# transfer-interconnect.net
KiCad netlist of a schematic drawn in EAGLE
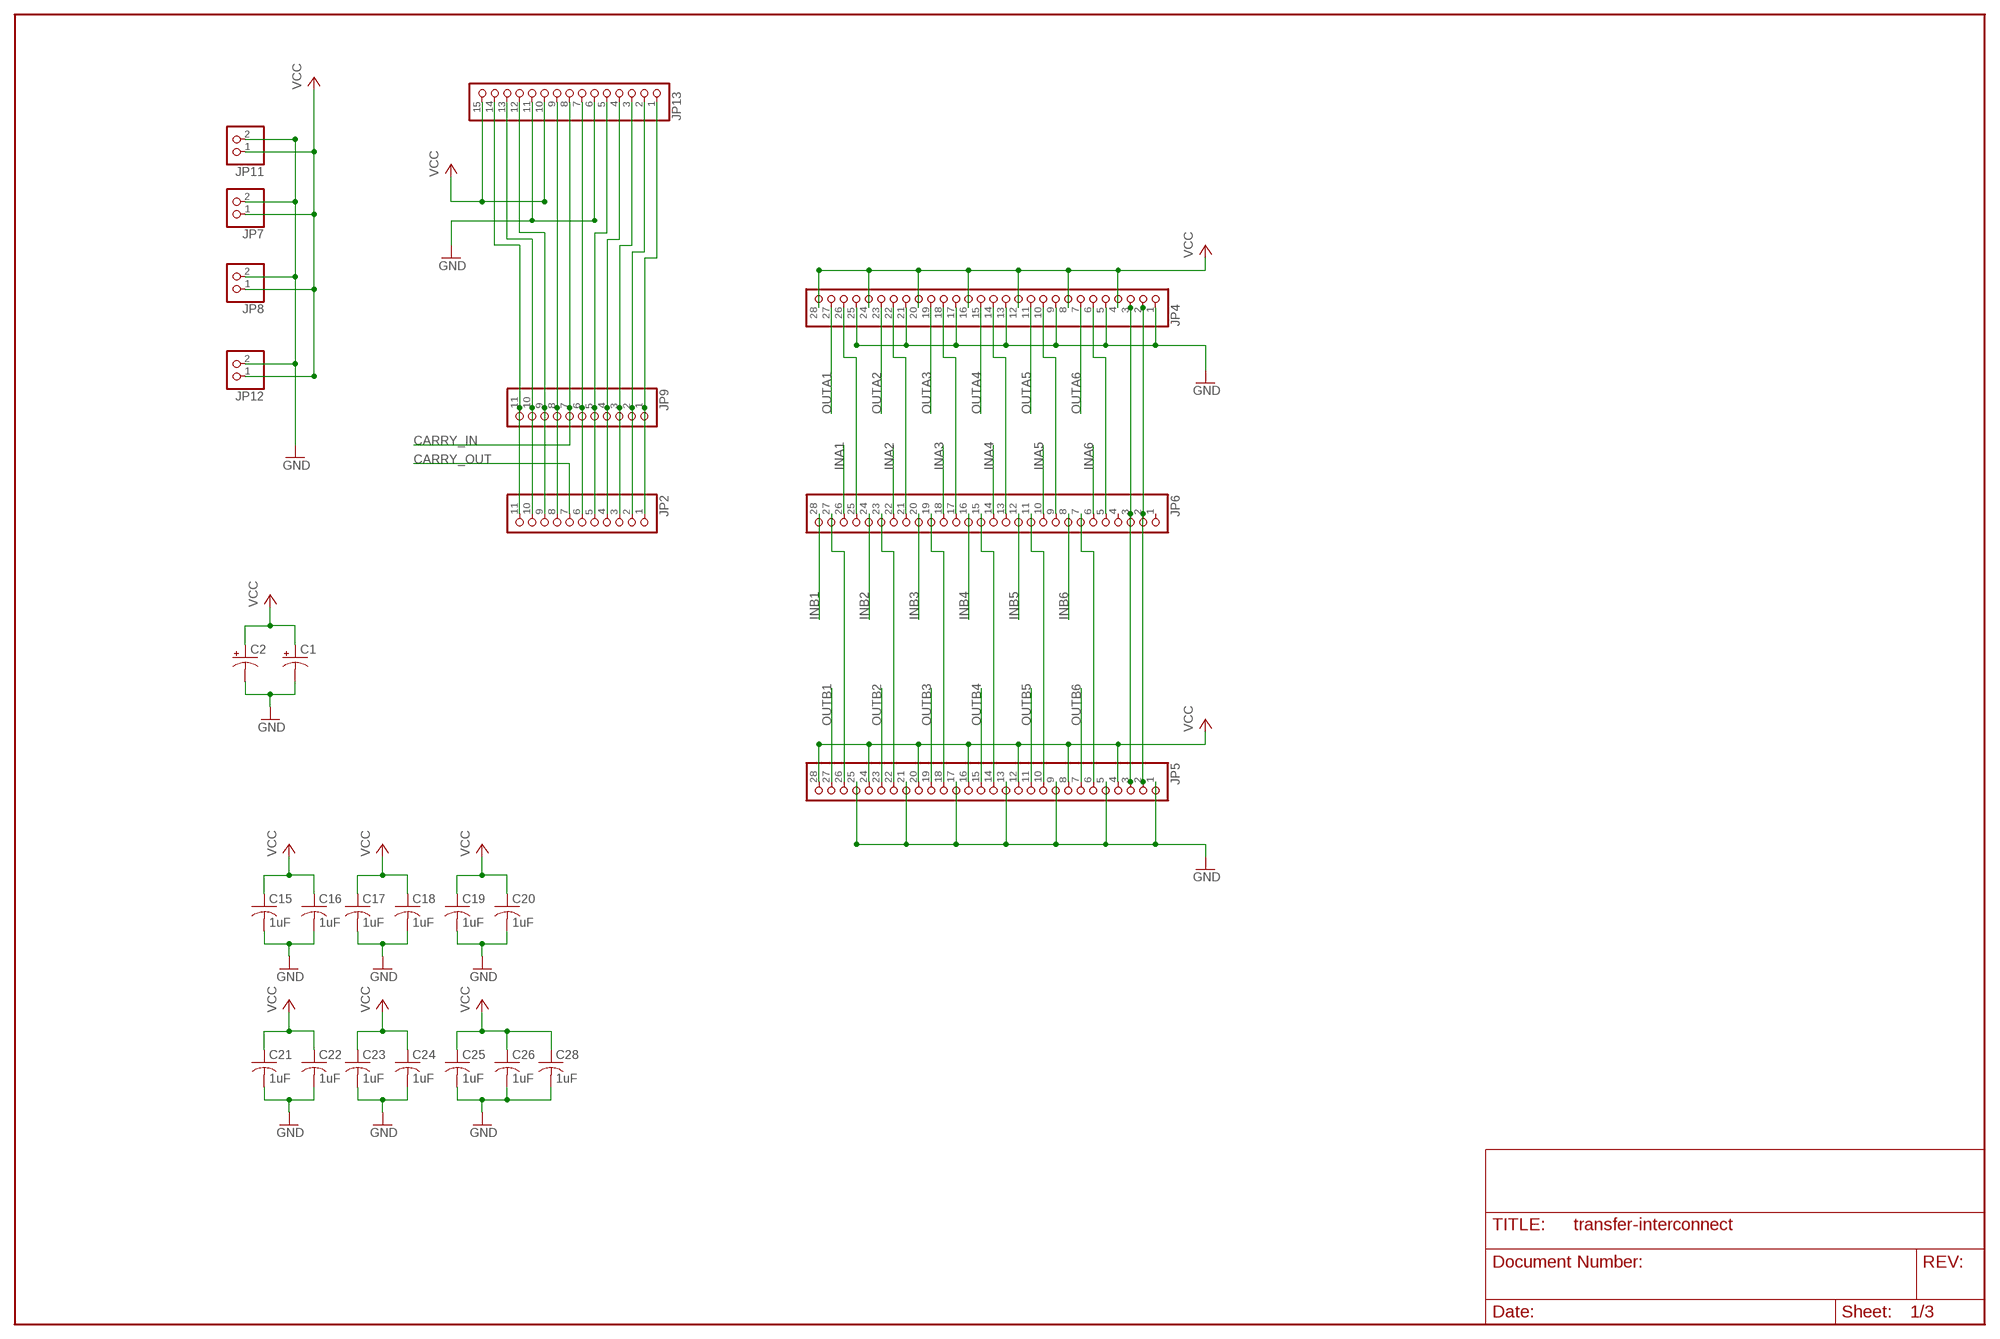
[diagram p0: schematic, sheet 1]
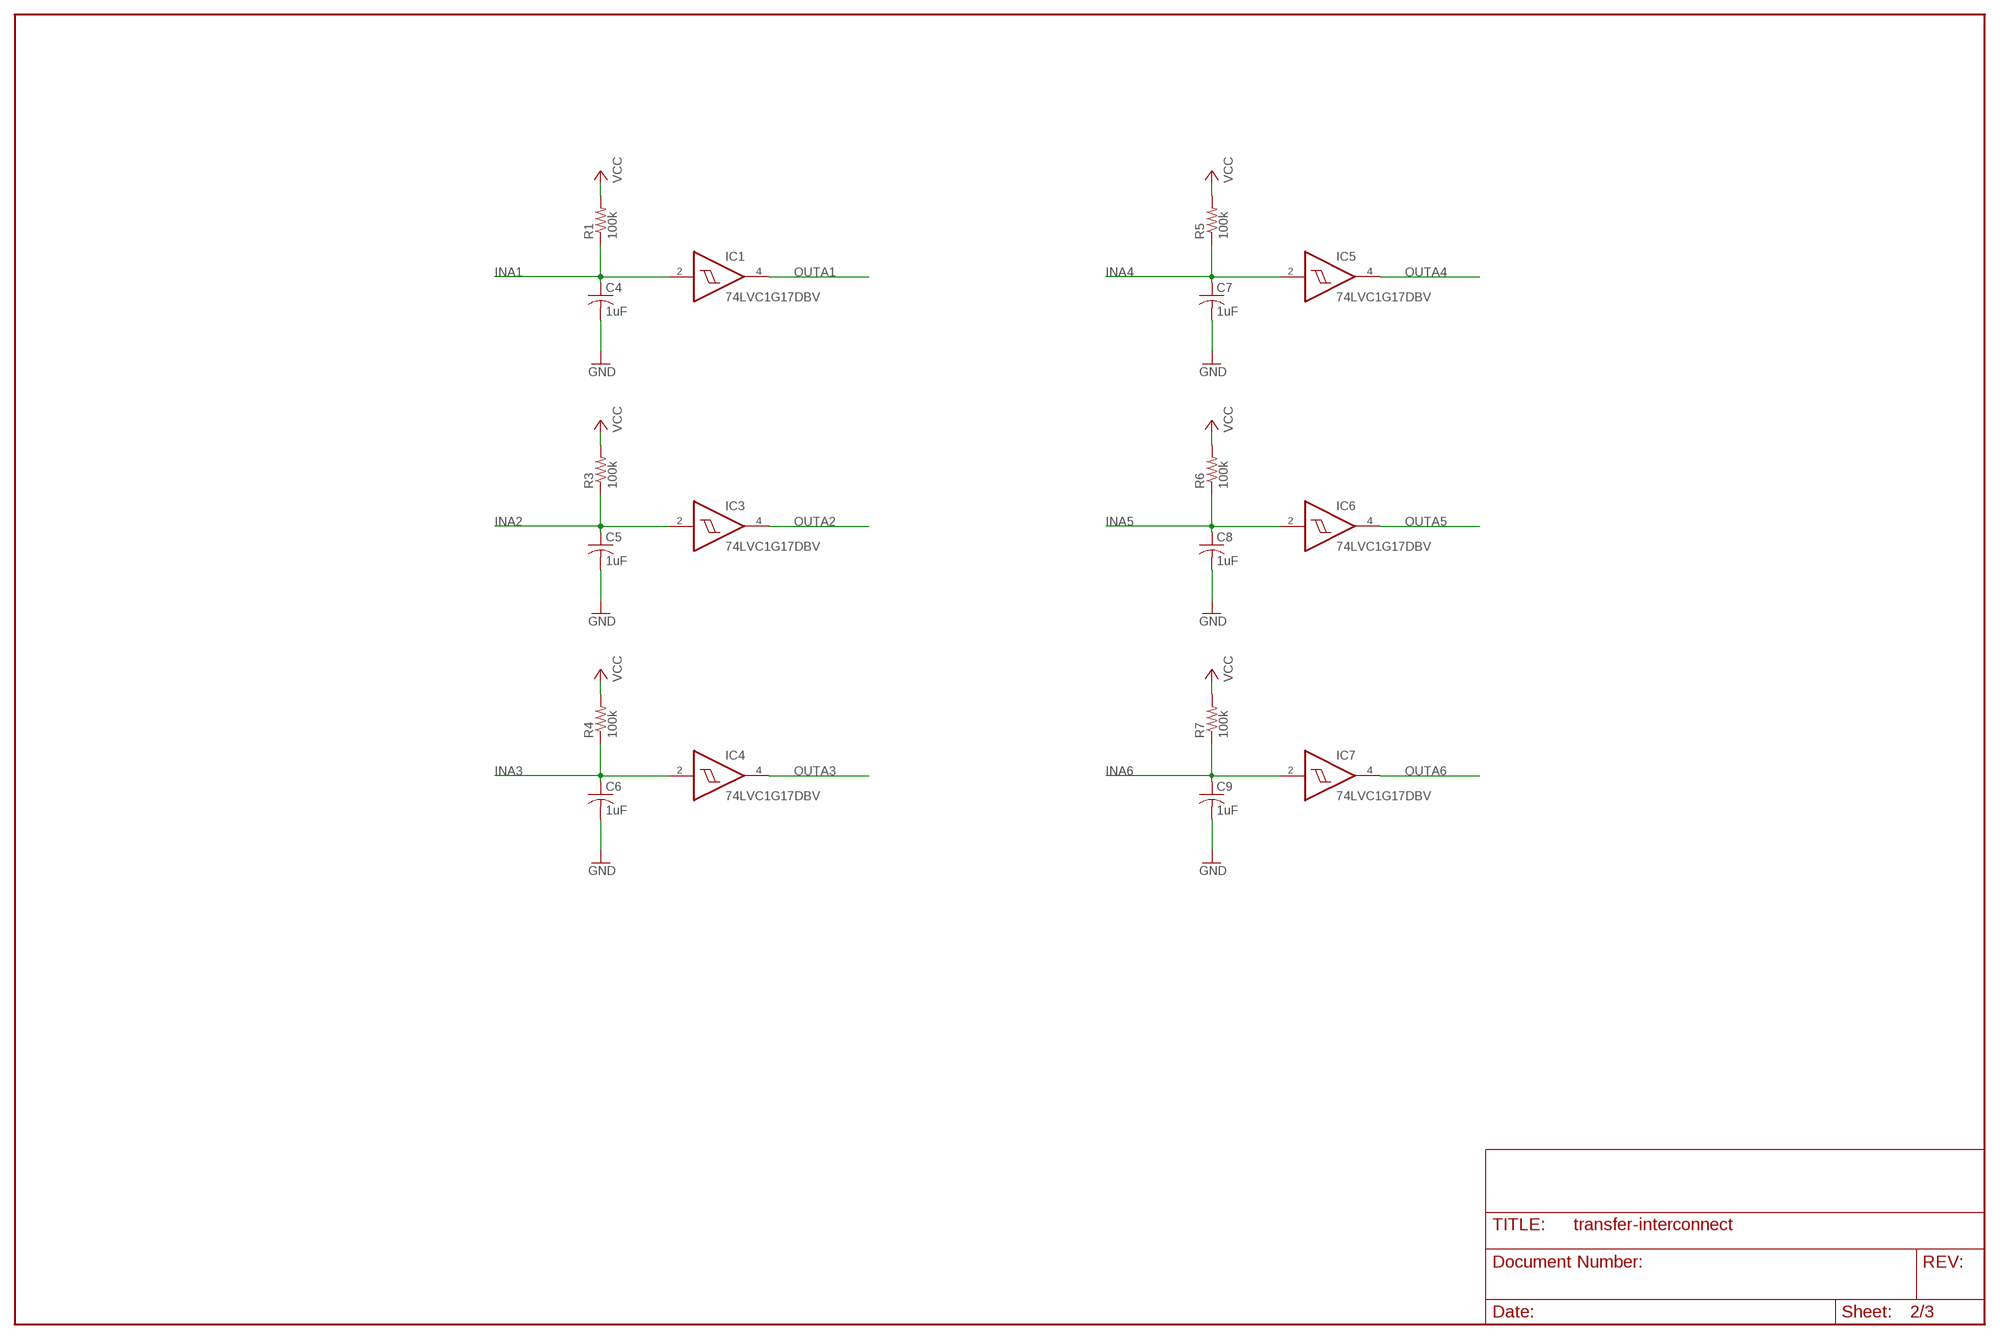
[diagram p1: schematic, sheet 2]
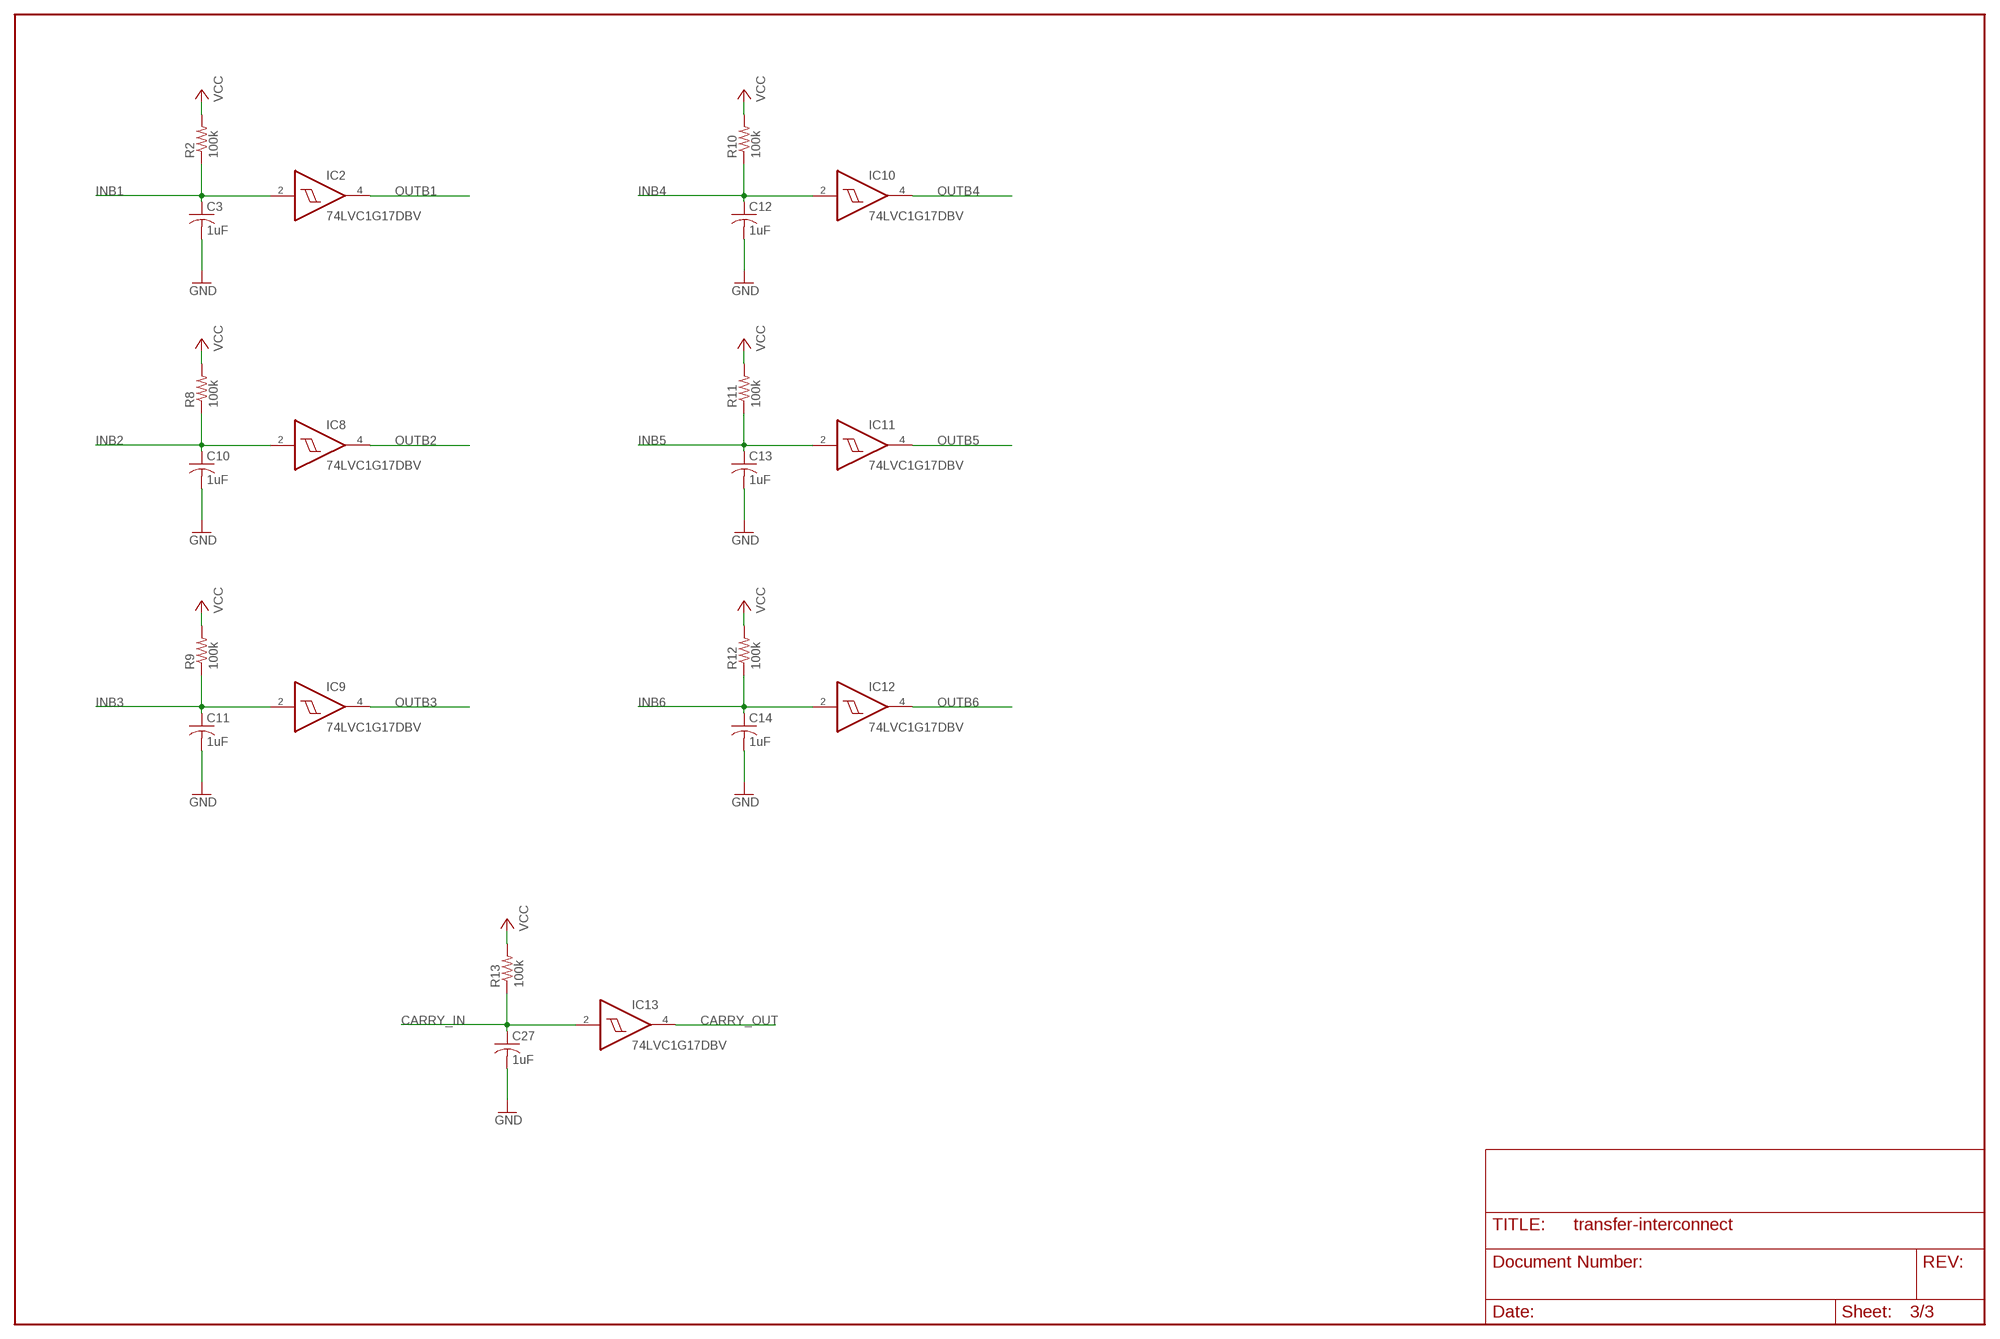
[diagram p2: schematic, sheet 3]

(export (version "E")
  (design (tool "Eeschema 10.0.6"))
  (components
    (comp (ref "C3")
      (value "1uF")
      (footprint "eagle-import:C0603K")
      (libsource (lib "eagle-import") (part "C-USC0603K"))
    )
    (comp (ref "C10")
      (value "1uF")
      (footprint "eagle-import:C0603K")
      (libsource (lib "eagle-import") (part "C-USC0603K"))
    )
    (comp (ref "C11")
      (value "1uF")
      (footprint "eagle-import:C0603K")
      (libsource (lib "eagle-import") (part "C-USC0603K"))
    )
    (comp (ref "C12")
      (value "1uF")
      (footprint "eagle-import:C0603K")
      (libsource (lib "eagle-import") (part "C-USC0603K"))
    )
    (comp (ref "C13")
      (value "1uF")
      (footprint "eagle-import:C0603K")
      (libsource (lib "eagle-import") (part "C-USC0603K"))
    )
    (comp (ref "C14")
      (value "1uF")
      (footprint "eagle-import:C0603K")
      (libsource (lib "eagle-import") (part "C-USC0603K"))
    )
    (comp (ref "C27")
      (value "1uF")
      (footprint "eagle-import:C0603K")
      (libsource (lib "eagle-import") (part "C-USC0603K"))
    )
    (comp (ref "IC2")
      (value "74LVC1G17DBV")
      (footprint "eagle-import:SOT23-5")
      (libsource (lib "eagle-import") (part "741G17DBVLVC"))
    )
    (comp (ref "IC8")
      (value "74LVC1G17DBV")
      (footprint "eagle-import:SOT23-5")
      (libsource (lib "eagle-import") (part "741G17DBVLVC"))
    )
    (comp (ref "IC9")
      (value "74LVC1G17DBV")
      (footprint "eagle-import:SOT23-5")
      (libsource (lib "eagle-import") (part "741G17DBVLVC"))
    )
    (comp (ref "IC10")
      (value "74LVC1G17DBV")
      (footprint "eagle-import:SOT23-5")
      (libsource (lib "eagle-import") (part "741G17DBVLVC"))
    )
    (comp (ref "IC11")
      (value "74LVC1G17DBV")
      (footprint "eagle-import:SOT23-5")
      (libsource (lib "eagle-import") (part "741G17DBVLVC"))
    )
    (comp (ref "IC12")
      (value "74LVC1G17DBV")
      (footprint "eagle-import:SOT23-5")
      (libsource (lib "eagle-import") (part "741G17DBVLVC"))
    )
    (comp (ref "IC13")
      (value "74LVC1G17DBV")
      (footprint "eagle-import:SOT23-5")
      (libsource (lib "eagle-import") (part "741G17DBVLVC"))
    )
    (comp (ref "R2")
      (value "100k")
      (footprint "eagle-import:R0603")
      (libsource (lib "eagle-import") (part "R-US_R0603"))
    )
    (comp (ref "R8")
      (value "100k")
      (footprint "eagle-import:R0603")
      (libsource (lib "eagle-import") (part "R-US_R0603"))
    )
    (comp (ref "R9")
      (value "100k")
      (footprint "eagle-import:R0603")
      (libsource (lib "eagle-import") (part "R-US_R0603"))
    )
    (comp (ref "R10")
      (value "100k")
      (footprint "eagle-import:R0603")
      (libsource (lib "eagle-import") (part "R-US_R0603"))
    )
    (comp (ref "R11")
      (value "100k")
      (footprint "eagle-import:R0603")
      (libsource (lib "eagle-import") (part "R-US_R0603"))
    )
    (comp (ref "R12")
      (value "100k")
      (footprint "eagle-import:R0603")
      (libsource (lib "eagle-import") (part "R-US_R0603"))
    )
    (comp (ref "R13")
      (value "100k")
      (footprint "eagle-import:R0603")
      (libsource (lib "eagle-import") (part "R-US_R0603"))
    )
    (comp (ref "C1")
      (value "CPOL-USE15-6AXIAL")
      (footprint "eagle-import:E15-6")
      (libsource (lib "eagle-import") (part "CPOL-USE15-6AXIAL"))
    )
    (comp (ref "C2")
      (value "CPOL-USE15-6AXIAL")
      (footprint "eagle-import:E15-6")
      (libsource (lib "eagle-import") (part "CPOL-USE15-6AXIAL"))
    )
    (comp (ref "C15")
      (value "1uF")
      (footprint "eagle-import:C0603K")
      (libsource (lib "eagle-import") (part "C-USC0603K"))
    )
    (comp (ref "C16")
      (value "1uF")
      (footprint "eagle-import:C0603K")
      (libsource (lib "eagle-import") (part "C-USC0603K"))
    )
    (comp (ref "C17")
      (value "1uF")
      (footprint "eagle-import:C0603K")
      (libsource (lib "eagle-import") (part "C-USC0603K"))
    )
    (comp (ref "C18")
      (value "1uF")
      (footprint "eagle-import:C0603K")
      (libsource (lib "eagle-import") (part "C-USC0603K"))
    )
    (comp (ref "C19")
      (value "1uF")
      (footprint "eagle-import:C0603K")
      (libsource (lib "eagle-import") (part "C-USC0603K"))
    )
    (comp (ref "C20")
      (value "1uF")
      (footprint "eagle-import:C0603K")
      (libsource (lib "eagle-import") (part "C-USC0603K"))
    )
    (comp (ref "C21")
      (value "1uF")
      (footprint "eagle-import:C0603K")
      (libsource (lib "eagle-import") (part "C-USC0603K"))
    )
    (comp (ref "C22")
      (value "1uF")
      (footprint "eagle-import:C0603K")
      (libsource (lib "eagle-import") (part "C-USC0603K"))
    )
    (comp (ref "C23")
      (value "1uF")
      (footprint "eagle-import:C0603K")
      (libsource (lib "eagle-import") (part "C-USC0603K"))
    )
    (comp (ref "C24")
      (value "1uF")
      (footprint "eagle-import:C0603K")
      (libsource (lib "eagle-import") (part "C-USC0603K"))
    )
    (comp (ref "C25")
      (value "1uF")
      (footprint "eagle-import:C0603K")
      (libsource (lib "eagle-import") (part "C-USC0603K"))
    )
    (comp (ref "C26")
      (value "1uF")
      (footprint "eagle-import:C0603K")
      (libsource (lib "eagle-import") (part "C-USC0603K"))
    )
    (comp (ref "C28")
      (value "1uF")
      (footprint "eagle-import:C0603K")
      (libsource (lib "eagle-import") (part "C-USC0603K"))
    )
    (comp (ref "JP2")
      (value "PINHD-1X11")
      (footprint "eagle-import:1X11")
      (libsource (lib "eagle-import") (part "PINHD-1X11"))
    )
    (comp (ref "JP4")
      (value "PINHD-1X28")
      (footprint "eagle-import:1X28")
      (libsource (lib "eagle-import") (part "PINHD-1X28"))
    )
    (comp (ref "JP5")
      (value "PINHD-1X28")
      (footprint "eagle-import:1X28")
      (libsource (lib "eagle-import") (part "PINHD-1X28"))
    )
    (comp (ref "JP6")
      (value "PINHD-1X28")
      (footprint "eagle-import:1X28")
      (libsource (lib "eagle-import") (part "PINHD-1X28"))
    )
    (comp (ref "JP7")
      (value "PINHD-1X2")
      (footprint "eagle-import:1X02")
      (libsource (lib "eagle-import") (part "PINHD-1X2"))
    )
    (comp (ref "JP8")
      (value "PINHD-1X2")
      (footprint "eagle-import:1X02")
      (libsource (lib "eagle-import") (part "PINHD-1X2"))
    )
    (comp (ref "JP9")
      (value "PINHD-1X11")
      (footprint "eagle-import:1X11")
      (libsource (lib "eagle-import") (part "PINHD-1X11"))
    )
    (comp (ref "JP11")
      (value "PINHD-1X2")
      (footprint "eagle-import:1X02")
      (libsource (lib "eagle-import") (part "PINHD-1X2"))
    )
    (comp (ref "JP12")
      (value "PINHD-1X2")
      (footprint "eagle-import:1X02")
      (libsource (lib "eagle-import") (part "PINHD-1X2"))
    )
    (comp (ref "JP13")
      (value "PINHD-1X15")
      (footprint "eagle-import:1X15")
      (libsource (lib "eagle-import") (part "PINHD-1X15"))
    )
    (comp (ref "C4")
      (value "1uF")
      (footprint "eagle-import:C0603K")
      (libsource (lib "eagle-import") (part "C-USC0603K"))
    )
    (comp (ref "C5")
      (value "1uF")
      (footprint "eagle-import:C0603K")
      (libsource (lib "eagle-import") (part "C-USC0603K"))
    )
    (comp (ref "C6")
      (value "1uF")
      (footprint "eagle-import:C0603K")
      (libsource (lib "eagle-import") (part "C-USC0603K"))
    )
    (comp (ref "C7")
      (value "1uF")
      (footprint "eagle-import:C0603K")
      (libsource (lib "eagle-import") (part "C-USC0603K"))
    )
    (comp (ref "C8")
      (value "1uF")
      (footprint "eagle-import:C0603K")
      (libsource (lib "eagle-import") (part "C-USC0603K"))
    )
    (comp (ref "C9")
      (value "1uF")
      (footprint "eagle-import:C0603K")
      (libsource (lib "eagle-import") (part "C-USC0603K"))
    )
    (comp (ref "IC1")
      (value "74LVC1G17DBV")
      (footprint "eagle-import:SOT23-5")
      (libsource (lib "eagle-import") (part "741G17DBVLVC"))
    )
    (comp (ref "IC3")
      (value "74LVC1G17DBV")
      (footprint "eagle-import:SOT23-5")
      (libsource (lib "eagle-import") (part "741G17DBVLVC"))
    )
    (comp (ref "IC4")
      (value "74LVC1G17DBV")
      (footprint "eagle-import:SOT23-5")
      (libsource (lib "eagle-import") (part "741G17DBVLVC"))
    )
    (comp (ref "IC5")
      (value "74LVC1G17DBV")
      (footprint "eagle-import:SOT23-5")
      (libsource (lib "eagle-import") (part "741G17DBVLVC"))
    )
    (comp (ref "IC6")
      (value "74LVC1G17DBV")
      (footprint "eagle-import:SOT23-5")
      (libsource (lib "eagle-import") (part "741G17DBVLVC"))
    )
    (comp (ref "IC7")
      (value "74LVC1G17DBV")
      (footprint "eagle-import:SOT23-5")
      (libsource (lib "eagle-import") (part "741G17DBVLVC"))
    )
    (comp (ref "R1")
      (value "100k")
      (footprint "eagle-import:R0603")
      (libsource (lib "eagle-import") (part "R-US_R0603"))
    )
    (comp (ref "R3")
      (value "100k")
      (footprint "eagle-import:R0603")
      (libsource (lib "eagle-import") (part "R-US_R0603"))
    )
    (comp (ref "R4")
      (value "100k")
      (footprint "eagle-import:R0603")
      (libsource (lib "eagle-import") (part "R-US_R0603"))
    )
    (comp (ref "R5")
      (value "100k")
      (footprint "eagle-import:R0603")
      (libsource (lib "eagle-import") (part "R-US_R0603"))
    )
    (comp (ref "R6")
      (value "100k")
      (footprint "eagle-import:R0603")
      (libsource (lib "eagle-import") (part "R-US_R0603"))
    )
    (comp (ref "R7")
      (value "100k")
      (footprint "eagle-import:R0603")
      (libsource (lib "eagle-import") (part "R-US_R0603"))
    )
  )
  (nets
    (net (code "1") (name "CARRY_IN") (class "Default")
      (node (ref "C27") (pin "1") (pinfunction "1_1") (pintype "passive"))
      (node (ref "IC13") (pin "2") (pinfunction "I_2") (pintype "input"))
      (node (ref "JP13") (pin "8") (pinfunction "8_8") (pintype "passive"))
      (node (ref "JP9") (pin "7") (pinfunction "7_7") (pintype "passive"))
      (node (ref "R13") (pin "1") (pinfunction "1_1") (pintype "passive"))
    )
    (net (code "2") (name "CARRY_OUT") (class "Default")
      (node (ref "IC13") (pin "4") (pinfunction "O_4") (pintype "output"))
      (node (ref "JP2") (pin "7") (pinfunction "7_7") (pintype "passive"))
    )
    (net (code "3") (name "GND") (class "Default")
      (node (ref "C1") (pin "-") (pinfunction "-_-") (pintype "passive"))
      (node (ref "C10") (pin "2") (pinfunction "2_2") (pintype "passive"))
      (node (ref "C11") (pin "2") (pinfunction "2_2") (pintype "passive"))
      (node (ref "C12") (pin "2") (pinfunction "2_2") (pintype "passive"))
      (node (ref "C13") (pin "2") (pinfunction "2_2") (pintype "passive"))
      (node (ref "C14") (pin "2") (pinfunction "2_2") (pintype "passive"))
      (node (ref "C15") (pin "2") (pinfunction "2_2") (pintype "passive"))
      (node (ref "C16") (pin "2") (pinfunction "2_2") (pintype "passive"))
      (node (ref "C17") (pin "2") (pinfunction "2_2") (pintype "passive"))
      (node (ref "C18") (pin "2") (pinfunction "2_2") (pintype "passive"))
      (node (ref "C19") (pin "2") (pinfunction "2_2") (pintype "passive"))
      (node (ref "C2") (pin "-") (pinfunction "-_-") (pintype "passive"))
      (node (ref "C20") (pin "2") (pinfunction "2_2") (pintype "passive"))
      (node (ref "C21") (pin "2") (pinfunction "2_2") (pintype "passive"))
      (node (ref "C22") (pin "2") (pinfunction "2_2") (pintype "passive"))
      (node (ref "C23") (pin "2") (pinfunction "2_2") (pintype "passive"))
      (node (ref "C24") (pin "2") (pinfunction "2_2") (pintype "passive"))
      (node (ref "C25") (pin "2") (pinfunction "2_2") (pintype "passive"))
      (node (ref "C26") (pin "2") (pinfunction "2_2") (pintype "passive"))
      (node (ref "C27") (pin "2") (pinfunction "2_2") (pintype "passive"))
      (node (ref "C28") (pin "2") (pinfunction "2_2") (pintype "passive"))
      (node (ref "C3") (pin "2") (pinfunction "2_2") (pintype "passive"))
      (node (ref "C4") (pin "2") (pinfunction "2_2") (pintype "passive"))
      (node (ref "C5") (pin "2") (pinfunction "2_2") (pintype "passive"))
      (node (ref "C6") (pin "2") (pinfunction "2_2") (pintype "passive"))
      (node (ref "C7") (pin "2") (pinfunction "2_2") (pintype "passive"))
      (node (ref "C8") (pin "2") (pinfunction "2_2") (pintype "passive"))
      (node (ref "C9") (pin "2") (pinfunction "2_2") (pintype "passive"))
      (node (ref "JP11") (pin "2") (pinfunction "2_2") (pintype "passive"))
      (node (ref "JP12") (pin "2") (pinfunction "2_2") (pintype "passive"))
      (node (ref "JP13") (pin "11") (pinfunction "11_11") (pintype "passive"))
      (node (ref "JP13") (pin "6") (pinfunction "6_6") (pintype "passive"))
      (node (ref "JP4") (pin "1") (pinfunction "1_1") (pintype "passive"))
      (node (ref "JP4") (pin "13") (pinfunction "13_13") (pintype "passive"))
      (node (ref "JP4") (pin "17") (pinfunction "17_17") (pintype "passive"))
      (node (ref "JP4") (pin "21") (pinfunction "21_21") (pintype "passive"))
      (node (ref "JP4") (pin "25") (pinfunction "25_25") (pintype "passive"))
      (node (ref "JP4") (pin "5") (pinfunction "5_5") (pintype "passive"))
      (node (ref "JP4") (pin "9") (pinfunction "9_9") (pintype "passive"))
      (node (ref "JP5") (pin "1") (pinfunction "1_1") (pintype "passive"))
      (node (ref "JP5") (pin "13") (pinfunction "13_13") (pintype "passive"))
      (node (ref "JP5") (pin "17") (pinfunction "17_17") (pintype "passive"))
      (node (ref "JP5") (pin "21") (pinfunction "21_21") (pintype "passive"))
      (node (ref "JP5") (pin "25") (pinfunction "25_25") (pintype "passive"))
      (node (ref "JP5") (pin "5") (pinfunction "5_5") (pintype "passive"))
      (node (ref "JP5") (pin "9") (pinfunction "9_9") (pintype "passive"))
      (node (ref "JP7") (pin "2") (pinfunction "2_2") (pintype "passive"))
      (node (ref "JP8") (pin "2") (pinfunction "2_2") (pintype "passive"))
    )
    (net (code "4") (name "INA1") (class "Default")
      (node (ref "C4") (pin "1") (pinfunction "1_1") (pintype "passive"))
      (node (ref "IC1") (pin "2") (pinfunction "I_2") (pintype "input"))
      (node (ref "JP6") (pin "26") (pinfunction "26_26") (pintype "passive"))
      (node (ref "R1") (pin "1") (pinfunction "1_1") (pintype "passive"))
    )
    (net (code "5") (name "INA2") (class "Default")
      (node (ref "C5") (pin "1") (pinfunction "1_1") (pintype "passive"))
      (node (ref "IC3") (pin "2") (pinfunction "I_2") (pintype "input"))
      (node (ref "JP6") (pin "22") (pinfunction "22_22") (pintype "passive"))
      (node (ref "R3") (pin "1") (pinfunction "1_1") (pintype "passive"))
    )
    (net (code "6") (name "INA3") (class "Default")
      (node (ref "C6") (pin "1") (pinfunction "1_1") (pintype "passive"))
      (node (ref "IC4") (pin "2") (pinfunction "I_2") (pintype "input"))
      (node (ref "JP6") (pin "18") (pinfunction "18_18") (pintype "passive"))
      (node (ref "R4") (pin "1") (pinfunction "1_1") (pintype "passive"))
    )
    (net (code "7") (name "INA4") (class "Default")
      (node (ref "C7") (pin "1") (pinfunction "1_1") (pintype "passive"))
      (node (ref "IC5") (pin "2") (pinfunction "I_2") (pintype "input"))
      (node (ref "JP6") (pin "14") (pinfunction "14_14") (pintype "passive"))
      (node (ref "R5") (pin "1") (pinfunction "1_1") (pintype "passive"))
    )
    (net (code "8") (name "INA5") (class "Default")
      (node (ref "C8") (pin "1") (pinfunction "1_1") (pintype "passive"))
      (node (ref "IC6") (pin "2") (pinfunction "I_2") (pintype "input"))
      (node (ref "JP6") (pin "10") (pinfunction "10_10") (pintype "passive"))
      (node (ref "R6") (pin "1") (pinfunction "1_1") (pintype "passive"))
    )
    (net (code "9") (name "INA6") (class "Default")
      (node (ref "C9") (pin "1") (pinfunction "1_1") (pintype "passive"))
      (node (ref "IC7") (pin "2") (pinfunction "I_2") (pintype "input"))
      (node (ref "JP6") (pin "6") (pinfunction "6_6") (pintype "passive"))
      (node (ref "R7") (pin "1") (pinfunction "1_1") (pintype "passive"))
    )
    (net (code "10") (name "INB1") (class "Default")
      (node (ref "C3") (pin "1") (pinfunction "1_1") (pintype "passive"))
      (node (ref "IC2") (pin "2") (pinfunction "I_2") (pintype "input"))
      (node (ref "JP6") (pin "28") (pinfunction "28_28") (pintype "passive"))
      (node (ref "R2") (pin "1") (pinfunction "1_1") (pintype "passive"))
    )
    (net (code "11") (name "INB2") (class "Default")
      (node (ref "C10") (pin "1") (pinfunction "1_1") (pintype "passive"))
      (node (ref "IC8") (pin "2") (pinfunction "I_2") (pintype "input"))
      (node (ref "JP6") (pin "24") (pinfunction "24_24") (pintype "passive"))
      (node (ref "R8") (pin "1") (pinfunction "1_1") (pintype "passive"))
    )
    (net (code "12") (name "INB3") (class "Default")
      (node (ref "C11") (pin "1") (pinfunction "1_1") (pintype "passive"))
      (node (ref "IC9") (pin "2") (pinfunction "I_2") (pintype "input"))
      (node (ref "JP6") (pin "20") (pinfunction "20_20") (pintype "passive"))
      (node (ref "R9") (pin "1") (pinfunction "1_1") (pintype "passive"))
    )
    (net (code "13") (name "INB4") (class "Default")
      (node (ref "C12") (pin "1") (pinfunction "1_1") (pintype "passive"))
      (node (ref "IC10") (pin "2") (pinfunction "I_2") (pintype "input"))
      (node (ref "JP6") (pin "16") (pinfunction "16_16") (pintype "passive"))
      (node (ref "R10") (pin "1") (pinfunction "1_1") (pintype "passive"))
    )
    (net (code "14") (name "INB5") (class "Default")
      (node (ref "C13") (pin "1") (pinfunction "1_1") (pintype "passive"))
      (node (ref "IC11") (pin "2") (pinfunction "I_2") (pintype "input"))
      (node (ref "JP6") (pin "12") (pinfunction "12_12") (pintype "passive"))
      (node (ref "R11") (pin "1") (pinfunction "1_1") (pintype "passive"))
    )
    (net (code "15") (name "INB6") (class "Default")
      (node (ref "C14") (pin "1") (pinfunction "1_1") (pintype "passive"))
      (node (ref "IC12") (pin "2") (pinfunction "I_2") (pintype "input"))
      (node (ref "JP6") (pin "8") (pinfunction "8_8") (pintype "passive"))
      (node (ref "R12") (pin "1") (pinfunction "1_1") (pintype "passive"))
    )
    (net (code "16") (name "Net-(JP4-Pad2)") (class "Default")
      (node (ref "JP4") (pin "2") (pinfunction "2_2") (pintype "passive"))
      (node (ref "JP5") (pin "2") (pinfunction "2_2") (pintype "passive"))
      (node (ref "JP6") (pin "2") (pinfunction "2_2") (pintype "passive"))
    )
    (net (code "17") (name "Net-(JP4-Pad3)") (class "Default")
      (node (ref "JP4") (pin "3") (pinfunction "3_3") (pintype "passive"))
      (node (ref "JP5") (pin "3") (pinfunction "3_3") (pintype "passive"))
      (node (ref "JP6") (pin "3") (pinfunction "3_3") (pintype "passive"))
    )
    (net (code "18") (name "Net-(JP4-Pad6)") (class "Default")
      (node (ref "JP4") (pin "6") (pinfunction "6_6") (pintype "passive"))
      (node (ref "JP6") (pin "5") (pinfunction "5_5") (pintype "passive"))
    )
    (net (code "19") (name "Net-(JP4-Pad10)") (class "Default")
      (node (ref "JP4") (pin "10") (pinfunction "10_10") (pintype "passive"))
      (node (ref "JP6") (pin "9") (pinfunction "9_9") (pintype "passive"))
    )
    (net (code "20") (name "Net-(JP4-Pad14)") (class "Default")
      (node (ref "JP4") (pin "14") (pinfunction "14_14") (pintype "passive"))
      (node (ref "JP6") (pin "13") (pinfunction "13_13") (pintype "passive"))
    )
    (net (code "21") (name "Net-(JP4-Pad18)") (class "Default")
      (node (ref "JP4") (pin "18") (pinfunction "18_18") (pintype "passive"))
      (node (ref "JP6") (pin "17") (pinfunction "17_17") (pintype "passive"))
    )
    (net (code "22") (name "Net-(JP4-Pad22)") (class "Default")
      (node (ref "JP4") (pin "22") (pinfunction "22_22") (pintype "passive"))
      (node (ref "JP6") (pin "21") (pinfunction "21_21") (pintype "passive"))
    )
    (net (code "23") (name "Net-(JP4-Pad26)") (class "Default")
      (node (ref "JP4") (pin "26") (pinfunction "26_26") (pintype "passive"))
      (node (ref "JP6") (pin "25") (pinfunction "25_25") (pintype "passive"))
    )
    (net (code "24") (name "Net-(JP5-Pad6)") (class "Default")
      (node (ref "JP5") (pin "6") (pinfunction "6_6") (pintype "passive"))
      (node (ref "JP6") (pin "7") (pinfunction "7_7") (pintype "passive"))
    )
    (net (code "25") (name "Net-(JP5-Pad10)") (class "Default")
      (node (ref "JP5") (pin "10") (pinfunction "10_10") (pintype "passive"))
      (node (ref "JP6") (pin "11") (pinfunction "11_11") (pintype "passive"))
    )
    (net (code "26") (name "Net-(JP5-Pad14)") (class "Default")
      (node (ref "JP5") (pin "14") (pinfunction "14_14") (pintype "passive"))
      (node (ref "JP6") (pin "15") (pinfunction "15_15") (pintype "passive"))
    )
    (net (code "27") (name "Net-(JP5-Pad18)") (class "Default")
      (node (ref "JP5") (pin "18") (pinfunction "18_18") (pintype "passive"))
      (node (ref "JP6") (pin "19") (pinfunction "19_19") (pintype "passive"))
    )
    (net (code "28") (name "Net-(JP5-Pad22)") (class "Default")
      (node (ref "JP5") (pin "22") (pinfunction "22_22") (pintype "passive"))
      (node (ref "JP6") (pin "23") (pinfunction "23_23") (pintype "passive"))
    )
    (net (code "29") (name "Net-(JP5-Pad26)") (class "Default")
      (node (ref "JP5") (pin "26") (pinfunction "26_26") (pintype "passive"))
      (node (ref "JP6") (pin "27") (pinfunction "27_27") (pintype "passive"))
    )
    (net (code "30") (name "Net-(JP13-Pad1)") (class "Default")
      (node (ref "JP13") (pin "1") (pinfunction "1_1") (pintype "passive"))
      (node (ref "JP2") (pin "1") (pinfunction "1_1") (pintype "passive"))
      (node (ref "JP9") (pin "1") (pinfunction "1_1") (pintype "passive"))
    )
    (net (code "31") (name "Net-(JP13-Pad2)") (class "Default")
      (node (ref "JP13") (pin "2") (pinfunction "2_2") (pintype "passive"))
      (node (ref "JP2") (pin "2") (pinfunction "2_2") (pintype "passive"))
      (node (ref "JP9") (pin "2") (pinfunction "2_2") (pintype "passive"))
    )
    (net (code "32") (name "Net-(JP13-Pad3)") (class "Default")
      (node (ref "JP13") (pin "3") (pinfunction "3_3") (pintype "passive"))
      (node (ref "JP2") (pin "3") (pinfunction "3_3") (pintype "passive"))
      (node (ref "JP9") (pin "3") (pinfunction "3_3") (pintype "passive"))
    )
    (net (code "33") (name "Net-(JP13-Pad4)") (class "Default")
      (node (ref "JP13") (pin "4") (pinfunction "4_4") (pintype "passive"))
      (node (ref "JP2") (pin "4") (pinfunction "4_4") (pintype "passive"))
      (node (ref "JP9") (pin "4") (pinfunction "4_4") (pintype "passive"))
    )
    (net (code "34") (name "Net-(JP13-Pad5)") (class "Default")
      (node (ref "JP13") (pin "5") (pinfunction "5_5") (pintype "passive"))
      (node (ref "JP2") (pin "5") (pinfunction "5_5") (pintype "passive"))
      (node (ref "JP9") (pin "5") (pinfunction "5_5") (pintype "passive"))
    )
    (net (code "35") (name "Net-(JP13-Pad7)") (class "Default")
      (node (ref "JP13") (pin "7") (pinfunction "7_7") (pintype "passive"))
      (node (ref "JP2") (pin "6") (pinfunction "6_6") (pintype "passive"))
      (node (ref "JP9") (pin "6") (pinfunction "6_6") (pintype "passive"))
    )
    (net (code "36") (name "Net-(JP13-Pad9)") (class "Default")
      (node (ref "JP13") (pin "9") (pinfunction "9_9") (pintype "passive"))
      (node (ref "JP2") (pin "8") (pinfunction "8_8") (pintype "passive"))
      (node (ref "JP9") (pin "8") (pinfunction "8_8") (pintype "passive"))
    )
    (net (code "37") (name "Net-(JP13-Pad12)") (class "Default")
      (node (ref "JP13") (pin "12") (pinfunction "12_12") (pintype "passive"))
      (node (ref "JP2") (pin "9") (pinfunction "9_9") (pintype "passive"))
      (node (ref "JP9") (pin "9") (pinfunction "9_9") (pintype "passive"))
    )
    (net (code "38") (name "Net-(JP13-Pad13)") (class "Default")
      (node (ref "JP13") (pin "13") (pinfunction "13_13") (pintype "passive"))
      (node (ref "JP2") (pin "10") (pinfunction "10_10") (pintype "passive"))
      (node (ref "JP9") (pin "10") (pinfunction "10_10") (pintype "passive"))
    )
    (net (code "39") (name "Net-(JP13-Pad14)") (class "Default")
      (node (ref "JP13") (pin "14") (pinfunction "14_14") (pintype "passive"))
      (node (ref "JP2") (pin "11") (pinfunction "11_11") (pintype "passive"))
      (node (ref "JP9") (pin "11") (pinfunction "11_11") (pintype "passive"))
    )
    (net (code "40") (name "OUTA1") (class "Default")
      (node (ref "IC1") (pin "4") (pinfunction "O_4") (pintype "output"))
      (node (ref "JP4") (pin "27") (pinfunction "27_27") (pintype "passive"))
    )
    (net (code "41") (name "OUTA2") (class "Default")
      (node (ref "IC3") (pin "4") (pinfunction "O_4") (pintype "output"))
      (node (ref "JP4") (pin "23") (pinfunction "23_23") (pintype "passive"))
    )
    (net (code "42") (name "OUTA3") (class "Default")
      (node (ref "IC4") (pin "4") (pinfunction "O_4") (pintype "output"))
      (node (ref "JP4") (pin "19") (pinfunction "19_19") (pintype "passive"))
    )
    (net (code "43") (name "OUTA4") (class "Default")
      (node (ref "IC5") (pin "4") (pinfunction "O_4") (pintype "output"))
      (node (ref "JP4") (pin "15") (pinfunction "15_15") (pintype "passive"))
    )
    (net (code "44") (name "OUTA5") (class "Default")
      (node (ref "IC6") (pin "4") (pinfunction "O_4") (pintype "output"))
      (node (ref "JP4") (pin "11") (pinfunction "11_11") (pintype "passive"))
    )
    (net (code "45") (name "OUTA6") (class "Default")
      (node (ref "IC7") (pin "4") (pinfunction "O_4") (pintype "output"))
      (node (ref "JP4") (pin "7") (pinfunction "7_7") (pintype "passive"))
    )
    (net (code "46") (name "OUTB1") (class "Default")
      (node (ref "IC2") (pin "4") (pinfunction "O_4") (pintype "output"))
      (node (ref "JP5") (pin "27") (pinfunction "27_27") (pintype "passive"))
    )
    (net (code "47") (name "OUTB2") (class "Default")
      (node (ref "IC8") (pin "4") (pinfunction "O_4") (pintype "output"))
      (node (ref "JP5") (pin "23") (pinfunction "23_23") (pintype "passive"))
    )
    (net (code "48") (name "OUTB3") (class "Default")
      (node (ref "IC9") (pin "4") (pinfunction "O_4") (pintype "output"))
      (node (ref "JP5") (pin "19") (pinfunction "19_19") (pintype "passive"))
    )
    (net (code "49") (name "OUTB4") (class "Default")
      (node (ref "IC10") (pin "4") (pinfunction "O_4") (pintype "output"))
      (node (ref "JP5") (pin "15") (pinfunction "15_15") (pintype "passive"))
    )
    (net (code "50") (name "OUTB5") (class "Default")
      (node (ref "IC11") (pin "4") (pinfunction "O_4") (pintype "output"))
      (node (ref "JP5") (pin "11") (pinfunction "11_11") (pintype "passive"))
    )
    (net (code "51") (name "OUTB6") (class "Default")
      (node (ref "IC12") (pin "4") (pinfunction "O_4") (pintype "output"))
      (node (ref "JP5") (pin "7") (pinfunction "7_7") (pintype "passive"))
    )
    (net (code "52") (name "VCC") (class "Default")
      (node (ref "C1") (pin "+") (pinfunction "+_+") (pintype "passive"))
      (node (ref "C15") (pin "1") (pinfunction "1_1") (pintype "passive"))
      (node (ref "C16") (pin "1") (pinfunction "1_1") (pintype "passive"))
      (node (ref "C17") (pin "1") (pinfunction "1_1") (pintype "passive"))
      (node (ref "C18") (pin "1") (pinfunction "1_1") (pintype "passive"))
      (node (ref "C19") (pin "1") (pinfunction "1_1") (pintype "passive"))
      (node (ref "C2") (pin "+") (pinfunction "+_+") (pintype "passive"))
      (node (ref "C20") (pin "1") (pinfunction "1_1") (pintype "passive"))
      (node (ref "C21") (pin "1") (pinfunction "1_1") (pintype "passive"))
      (node (ref "C22") (pin "1") (pinfunction "1_1") (pintype "passive"))
      (node (ref "C23") (pin "1") (pinfunction "1_1") (pintype "passive"))
      (node (ref "C24") (pin "1") (pinfunction "1_1") (pintype "passive"))
      (node (ref "C25") (pin "1") (pinfunction "1_1") (pintype "passive"))
      (node (ref "C26") (pin "1") (pinfunction "1_1") (pintype "passive"))
      (node (ref "C28") (pin "1") (pinfunction "1_1") (pintype "passive"))
      (node (ref "JP11") (pin "1") (pinfunction "1_1") (pintype "passive"))
      (node (ref "JP12") (pin "1") (pinfunction "1_1") (pintype "passive"))
      (node (ref "JP13") (pin "10") (pinfunction "10_10") (pintype "passive"))
      (node (ref "JP13") (pin "15") (pinfunction "15_15") (pintype "passive"))
      (node (ref "JP4") (pin "12") (pinfunction "12_12") (pintype "passive"))
      (node (ref "JP4") (pin "16") (pinfunction "16_16") (pintype "passive"))
      (node (ref "JP4") (pin "20") (pinfunction "20_20") (pintype "passive"))
      (node (ref "JP4") (pin "24") (pinfunction "24_24") (pintype "passive"))
      (node (ref "JP4") (pin "28") (pinfunction "28_28") (pintype "passive"))
      (node (ref "JP4") (pin "4") (pinfunction "4_4") (pintype "passive"))
      (node (ref "JP4") (pin "8") (pinfunction "8_8") (pintype "passive"))
      (node (ref "JP5") (pin "12") (pinfunction "12_12") (pintype "passive"))
      (node (ref "JP5") (pin "16") (pinfunction "16_16") (pintype "passive"))
      (node (ref "JP5") (pin "20") (pinfunction "20_20") (pintype "passive"))
      (node (ref "JP5") (pin "24") (pinfunction "24_24") (pintype "passive"))
      (node (ref "JP5") (pin "28") (pinfunction "28_28") (pintype "passive"))
      (node (ref "JP5") (pin "4") (pinfunction "4_4") (pintype "passive"))
      (node (ref "JP5") (pin "8") (pinfunction "8_8") (pintype "passive"))
      (node (ref "JP7") (pin "1") (pinfunction "1_1") (pintype "passive"))
      (node (ref "JP8") (pin "1") (pinfunction "1_1") (pintype "passive"))
      (node (ref "R1") (pin "2") (pinfunction "2_2") (pintype "passive"))
      (node (ref "R10") (pin "2") (pinfunction "2_2") (pintype "passive"))
      (node (ref "R11") (pin "2") (pinfunction "2_2") (pintype "passive"))
      (node (ref "R12") (pin "2") (pinfunction "2_2") (pintype "passive"))
      (node (ref "R13") (pin "2") (pinfunction "2_2") (pintype "passive"))
      (node (ref "R2") (pin "2") (pinfunction "2_2") (pintype "passive"))
      (node (ref "R3") (pin "2") (pinfunction "2_2") (pintype "passive"))
      (node (ref "R4") (pin "2") (pinfunction "2_2") (pintype "passive"))
      (node (ref "R5") (pin "2") (pinfunction "2_2") (pintype "passive"))
      (node (ref "R6") (pin "2") (pinfunction "2_2") (pintype "passive"))
      (node (ref "R7") (pin "2") (pinfunction "2_2") (pintype "passive"))
      (node (ref "R8") (pin "2") (pinfunction "2_2") (pintype "passive"))
      (node (ref "R9") (pin "2") (pinfunction "2_2") (pintype "passive"))
    )
    (net (code "53") (name "unconnected-(JP6-Pad1)") (class "Default")
      (node (ref "JP6") (pin "1") (pinfunction "1_1") (pintype "passive"))
    )
    (net (code "54") (name "unconnected-(JP6-Pad4)") (class "Default")
      (node (ref "JP6") (pin "4") (pinfunction "4_4") (pintype "passive"))
    )
  )
)
